# ATTEMP-Schematic.net
KiCad netlist of a schematic drawn in EAGLE
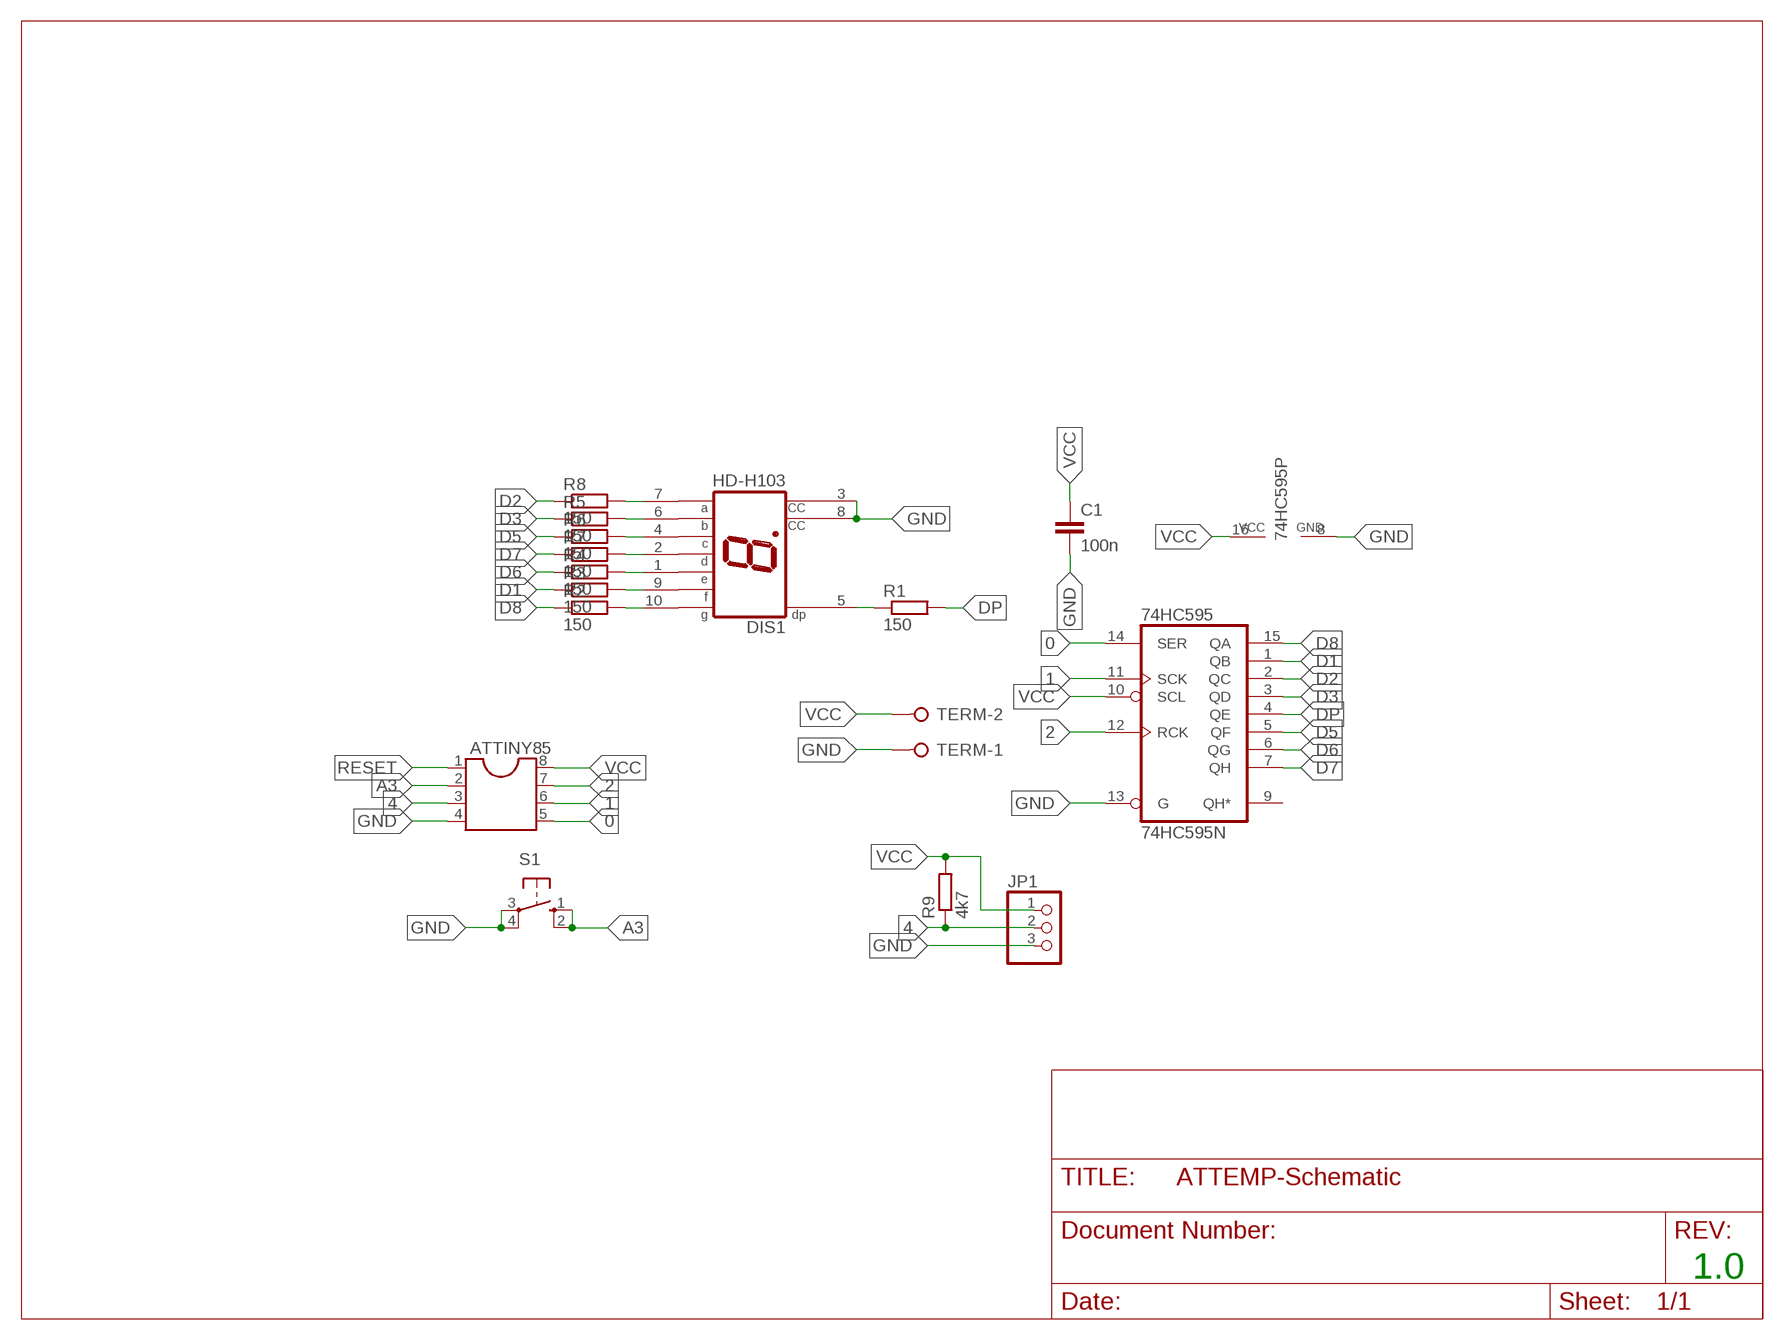
[diagram p0: schematic, sheet 1]

(export (version "E")
  (design (tool "Eeschema 10.0.6"))
  (components
    (comp (ref "74HC595")
      (value "74HC595N")
      (footprint "eagle-import:DIL16")
      (libsource (lib "eagle-import") (part "74595NHC"))
    )
    (comp (ref "ATTINY85")
      (value "DIL8")
      (footprint "eagle-import:DIL08")
      (libsource (lib "eagle-import") (part "DIL8"))
    )
    (comp (ref "C1")
      (value "100n")
      (footprint "eagle-import:C1206")
      (libsource (lib "eagle-import") (part "C-EUC1206"))
    )
    (comp (ref "DIS1")
      (value "HD-H103")
      (footprint "eagle-import:HDSP-M")
      (libsource (lib "eagle-import") (part "HD-H103"))
    )
    (comp (ref "JP1")
      (value "PINHD-1X3")
      (footprint "eagle-import:1X03")
      (libsource (lib "eagle-import") (part "PINHD-1X3"))
    )
    (comp (ref "R1")
      (value "150")
      (footprint "eagle-import:R1206")
      (libsource (lib "eagle-import") (part "R-EU_R1206"))
    )
    (comp (ref "R2")
      (value "150")
      (footprint "eagle-import:R1206")
      (libsource (lib "eagle-import") (part "R-EU_R1206"))
    )
    (comp (ref "R3")
      (value "150")
      (footprint "eagle-import:R1206")
      (libsource (lib "eagle-import") (part "R-EU_R1206"))
    )
    (comp (ref "R4")
      (value "150")
      (footprint "eagle-import:R1206")
      (libsource (lib "eagle-import") (part "R-EU_R1206"))
    )
    (comp (ref "R5")
      (value "150")
      (footprint "eagle-import:R1206")
      (libsource (lib "eagle-import") (part "R-EU_R1206"))
    )
    (comp (ref "R6")
      (value "150")
      (footprint "eagle-import:R1206")
      (libsource (lib "eagle-import") (part "R-EU_R1206"))
    )
    (comp (ref "R7")
      (value "150")
      (footprint "eagle-import:R1206")
      (libsource (lib "eagle-import") (part "R-EU_R1206"))
    )
    (comp (ref "R8")
      (value "150")
      (footprint "eagle-import:R1206")
      (libsource (lib "eagle-import") (part "R-EU_R1206"))
    )
    (comp (ref "R9")
      (value "4k7")
      (footprint "eagle-import:R1206")
      (libsource (lib "eagle-import") (part "R-EU_R1206"))
    )
    (comp (ref "S1")
      (value "10-XX")
      (footprint "eagle-import:B3F-10XX")
      (fields (field (name "MPN") "B3F-1000"))
      (libsource (lib "eagle-import") (part "10-XX"))
    )
    (comp (ref "TERM")
      (value "W237-02P")
      (footprint "eagle-import:W237-132")
      (libsource (lib "eagle-import") (part "W237-02P"))
    )
  )
  (nets
    (net (code "1") (name "0") (class "Default")
      (node (ref "74HC595") (pin "14") (pinfunction "SER_14") (pintype "input"))
      (node (ref "ATTINY85") (pin "5") (pinfunction "5_5") (pintype "passive"))
    )
    (net (code "2") (name "1") (class "Default")
      (node (ref "74HC595") (pin "11") (pinfunction "SCK_11") (pintype "input"))
      (node (ref "ATTINY85") (pin "6") (pinfunction "6_6") (pintype "passive"))
    )
    (net (code "3") (name "2") (class "Default")
      (node (ref "74HC595") (pin "12") (pinfunction "RCK_12") (pintype "input"))
      (node (ref "ATTINY85") (pin "7") (pinfunction "7_7") (pintype "passive"))
    )
    (net (code "4") (name "4") (class "Default")
      (node (ref "ATTINY85") (pin "3") (pinfunction "3_3") (pintype "passive"))
      (node (ref "JP1") (pin "2") (pinfunction "2_2") (pintype "passive"))
      (node (ref "R9") (pin "1") (pinfunction "1_1") (pintype "passive"))
    )
    (net (code "5") (name "A3") (class "Default")
      (node (ref "ATTINY85") (pin "2") (pinfunction "2_2") (pintype "passive"))
      (node (ref "S1") (pin "1") (pinfunction "S_1") (pintype "passive"))
      (node (ref "S1") (pin "2") (pinfunction "S1_2") (pintype "passive"))
    )
    (net (code "6") (name "D1") (class "Default")
      (node (ref "74HC595") (pin "1") (pinfunction "QB_1") (pintype "tri_state"))
      (node (ref "R3") (pin "1") (pinfunction "1_1") (pintype "passive"))
    )
    (net (code "7") (name "D2") (class "Default")
      (node (ref "74HC595") (pin "2") (pinfunction "QC_2") (pintype "tri_state"))
      (node (ref "R8") (pin "1") (pinfunction "1_1") (pintype "passive"))
    )
    (net (code "8") (name "D3") (class "Default")
      (node (ref "74HC595") (pin "3") (pinfunction "QD_3") (pintype "tri_state"))
      (node (ref "R5") (pin "1") (pinfunction "1_1") (pintype "passive"))
    )
    (net (code "9") (name "D5") (class "Default")
      (node (ref "74HC595") (pin "5") (pinfunction "QF_5") (pintype "tri_state"))
      (node (ref "R6") (pin "1") (pinfunction "1_1") (pintype "passive"))
    )
    (net (code "10") (name "D6") (class "Default")
      (node (ref "74HC595") (pin "6") (pinfunction "QG_6") (pintype "tri_state"))
      (node (ref "R4") (pin "1") (pinfunction "1_1") (pintype "passive"))
    )
    (net (code "11") (name "D7") (class "Default")
      (node (ref "74HC595") (pin "7") (pinfunction "QH_7") (pintype "tri_state"))
      (node (ref "R7") (pin "1") (pinfunction "1_1") (pintype "passive"))
    )
    (net (code "12") (name "D8") (class "Default")
      (node (ref "74HC595") (pin "15") (pinfunction "QA_15") (pintype "tri_state"))
      (node (ref "R2") (pin "1") (pinfunction "1_1") (pintype "passive"))
    )
    (net (code "13") (name "DP") (class "Default")
      (node (ref "74HC595") (pin "4") (pinfunction "QE_4") (pintype "tri_state"))
      (node (ref "R1") (pin "2") (pinfunction "2_2") (pintype "passive"))
    )
    (net (code "14") (name "GND") (class "Default")
      (node (ref "74HC595") (pin "13") (pinfunction "G_13") (pintype "input"))
      (node (ref "74HC595") (pin "8") (pinfunction "GND_8") (pintype "power_in"))
      (node (ref "ATTINY85") (pin "4") (pinfunction "4_4") (pintype "passive"))
      (node (ref "C1") (pin "2") (pinfunction "2_2") (pintype "passive"))
      (node (ref "DIS1") (pin "3") (pinfunction "CC_3") (pintype "passive"))
      (node (ref "DIS1") (pin "8") (pinfunction "CC_8") (pintype "passive"))
      (node (ref "JP1") (pin "3") (pinfunction "3_3") (pintype "passive"))
      (node (ref "S1") (pin "3") (pinfunction "P_3") (pintype "passive"))
      (node (ref "S1") (pin "4") (pinfunction "P1_4") (pintype "passive"))
      (node (ref "TERM") (pin "1") (pinfunction "KL_1") (pintype "passive"))
    )
    (net (code "15") (name "Net-(DIS1-A)") (class "Default")
      (node (ref "DIS1") (pin "7") (pinfunction "A_7") (pintype "passive"))
      (node (ref "R8") (pin "2") (pinfunction "2_2") (pintype "passive"))
    )
    (net (code "16") (name "Net-(DIS1-B)") (class "Default")
      (node (ref "DIS1") (pin "6") (pinfunction "B_6") (pintype "passive"))
      (node (ref "R5") (pin "2") (pinfunction "2_2") (pintype "passive"))
    )
    (net (code "17") (name "Net-(DIS1-C)") (class "Default")
      (node (ref "DIS1") (pin "4") (pinfunction "C_4") (pintype "passive"))
      (node (ref "R6") (pin "2") (pinfunction "2_2") (pintype "passive"))
    )
    (net (code "18") (name "Net-(DIS1-D)") (class "Default")
      (node (ref "DIS1") (pin "2") (pinfunction "D_2") (pintype "passive"))
      (node (ref "R7") (pin "2") (pinfunction "2_2") (pintype "passive"))
    )
    (net (code "19") (name "Net-(DIS1-DP)") (class "Default")
      (node (ref "DIS1") (pin "5") (pinfunction "DP_5") (pintype "passive"))
      (node (ref "R1") (pin "1") (pinfunction "1_1") (pintype "passive"))
    )
    (net (code "20") (name "Net-(DIS1-E)") (class "Default")
      (node (ref "DIS1") (pin "1") (pinfunction "E_1") (pintype "passive"))
      (node (ref "R4") (pin "2") (pinfunction "2_2") (pintype "passive"))
    )
    (net (code "21") (name "Net-(DIS1-F)") (class "Default")
      (node (ref "DIS1") (pin "9") (pinfunction "F_9") (pintype "passive"))
      (node (ref "R3") (pin "2") (pinfunction "2_2") (pintype "passive"))
    )
    (net (code "22") (name "Net-(DIS1-G)") (class "Default")
      (node (ref "DIS1") (pin "10") (pinfunction "G_10") (pintype "passive"))
      (node (ref "R2") (pin "2") (pinfunction "2_2") (pintype "passive"))
    )
    (net (code "23") (name "RESET") (class "Default")
      (node (ref "ATTINY85") (pin "1") (pinfunction "1_1") (pintype "passive"))
    )
    (net (code "24") (name "VCC") (class "Default")
      (node (ref "74HC595") (pin "10") (pinfunction "SCL_10") (pintype "input"))
      (node (ref "74HC595") (pin "16") (pinfunction "VCC_16") (pintype "power_in"))
      (node (ref "ATTINY85") (pin "8") (pinfunction "8_8") (pintype "passive"))
      (node (ref "C1") (pin "1") (pinfunction "1_1") (pintype "passive"))
      (node (ref "JP1") (pin "1") (pinfunction "1_1") (pintype "passive"))
      (node (ref "R9") (pin "2") (pinfunction "2_2") (pintype "passive"))
      (node (ref "TERM") (pin "2") (pinfunction "KL_2") (pintype "passive"))
    )
    (net (code "25") (name "unconnected-(74HC595A-QH*-Pad9)") (class "Default")
      (node (ref "74HC595") (pin "9") (pinfunction "QH*_9") (pintype "tri_state"))
    )
  )
)
